# Multivibrator.net
KiCad netlist of a schematic drawn in Altium Designer
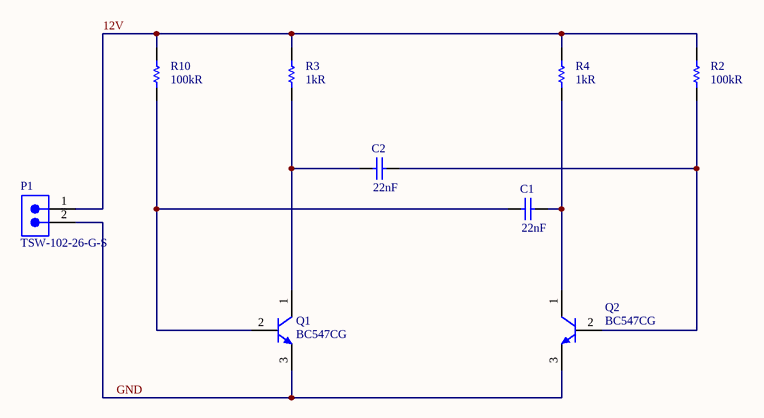
[diagram p0: Multivibrator.SchDoc]

(export (version "E")
  (design (tool "Eeschema 10.0.6"))
  (components
    (comp (ref "C1")
      (value "C0603C223K4RACTU")
      (footprint "CAPC1608X87X35ML15T15")
      (fields (field (name "MANUFACTURER") "Kemet") (field (name "CAPACITANCE") "22nF"))
      (libsource (lib "Altium Content Vault") (part "CAP"))
    )
    (comp (ref "C2")
      (value "C0603C223K4RACTU")
      (footprint "CAPC1608X87X35ML15T15")
      (fields (field (name "MANUFACTURER") "Kemet") (field (name "CAPACITANCE") "22nF"))
      (libsource (lib "Altium Content Vault") (part "CAP"))
    )
    (comp (ref "P1")
      (value "TSW-102-26-G-S")
      (footprint "SMTC-TSW-102-26-XX-S")
      (description "0.025\" SQ Post Header, Through-hole, Vertical, -55 to 125 degC, 2.54 mm Pitch, 2-Pin, Male, RoHS")
      (fields (field (name "MANUFACTURER") "Samtec"))
      (libsource (lib "Altium Content Vault") (part "SMTC-TSW-102-X-X-S-X"))
    )
    (comp (ref "Q1")
      (value "BC547CG")
      (footprint "ONSC-TO-92-3-29-11")
      (description "Amplifier Transistor, NPN Silicon, 3-Pin TO-92, Pb-Free, Bulk Box")
      (fields (field (name "MANUFACTURER") "On Semiconductor"))
      (libsource (lib "Altium Content Vault") (part "ONSC-NPN-C1B2E3-3"))
    )
    (comp (ref "Q2")
      (value "BC547CG")
      (footprint "ONSC-TO-92-3-29-11")
      (description "Amplifier Transistor, NPN Silicon, 3-Pin TO-92, Pb-Free, Bulk Box")
      (fields (field (name "MANUFACTURER") "On Semiconductor"))
      (libsource (lib "Altium Content Vault") (part "ONSC-NPN-C1B2E3-3"))
    )
    (comp (ref "R2")
      (value "ERJ-6GEYJ104V")
      (footprint "RESC2013X70X40ML20T20")
      (fields
        (field (name "MANUFACTURER") "Panasonic")
        (field (name "RESISTANCE") "100kR")
        (field (name "TOLERANCE") "5%")
      )
      (libsource (lib "Altium Content Vault") (part "RES"))
    )
    (comp (ref "R3")
      (value "CRCW08051K00JNEA")
      (footprint "RESC2013X50X30ML20T20")
      (fields
        (field (name "MANUFACTURER") "Vishay Dale")
        (field (name "RESISTANCE") "1kR")
        (field (name "TOLERANCE") "5%")
      )
      (libsource (lib "Altium Content Vault") (part "RES"))
    )
    (comp (ref "R4")
      (value "CRCW08051K00JNEA")
      (footprint "RESC2013X50X30ML20T20")
      (fields
        (field (name "MANUFACTURER") "Vishay Dale")
        (field (name "RESISTANCE") "1kR")
        (field (name "TOLERANCE") "5%")
      )
      (libsource (lib "Altium Content Vault") (part "RES"))
    )
    (comp (ref "R10")
      (value "ERJ-6GEYJ104V")
      (footprint "RESC2013X70X40ML20T20")
      (fields
        (field (name "MANUFACTURER") "Panasonic")
        (field (name "RESISTANCE") "100kR")
        (field (name "TOLERANCE") "5%")
      )
      (libsource (lib "Altium Content Vault") (part "RES"))
    )
  )
  (nets
    (net (code "1") (name "/12V") (class "Default")
      (node (ref "P1") (pin "1") (pinfunction "1_1") (pintype "passive"))
      (node (ref "R10") (pin "2") (pinfunction "2_2") (pintype "passive"))
      (node (ref "R2") (pin "2") (pinfunction "2_2") (pintype "passive"))
      (node (ref "R3") (pin "2") (pinfunction "2_2") (pintype "passive"))
      (node (ref "R4") (pin "2") (pinfunction "2_2") (pintype "passive"))
    )
    (net (code "2") (name "/GND") (class "Default")
      (node (ref "P1") (pin "2") (pinfunction "2_2") (pintype "passive"))
      (node (ref "Q1") (pin "3") (pinfunction "E_3") (pintype "passive"))
      (node (ref "Q2") (pin "3") (pinfunction "E_3") (pintype "passive"))
    )
    (net (code "3") (name "Net-(Q1-B)") (class "Default")
      (node (ref "C1") (pin "1") (pinfunction "1_1") (pintype "passive"))
      (node (ref "Q1") (pin "2") (pinfunction "B_2") (pintype "passive"))
      (node (ref "R10") (pin "1") (pinfunction "1_1") (pintype "passive"))
    )
    (net (code "4") (name "Net-(Q1-C)") (class "Default")
      (node (ref "C2") (pin "1") (pinfunction "1_1") (pintype "passive"))
      (node (ref "Q1") (pin "1") (pinfunction "C_1") (pintype "passive"))
      (node (ref "R3") (pin "1") (pinfunction "1_1") (pintype "passive"))
    )
    (net (code "5") (name "Net-(Q2-B)") (class "Default")
      (node (ref "C2") (pin "2") (pinfunction "2_2") (pintype "passive"))
      (node (ref "Q2") (pin "2") (pinfunction "B_2") (pintype "passive"))
      (node (ref "R2") (pin "1") (pinfunction "1_1") (pintype "passive"))
    )
    (net (code "6") (name "Net-(Q2-C)") (class "Default")
      (node (ref "C1") (pin "2") (pinfunction "2_2") (pintype "passive"))
      (node (ref "Q2") (pin "1") (pinfunction "C_1") (pintype "passive"))
      (node (ref "R4") (pin "1") (pinfunction "1_1") (pintype "passive"))
    )
  )
)
